# PowerBrick.net
KiCad netlist of a schematic drawn in EAGLE
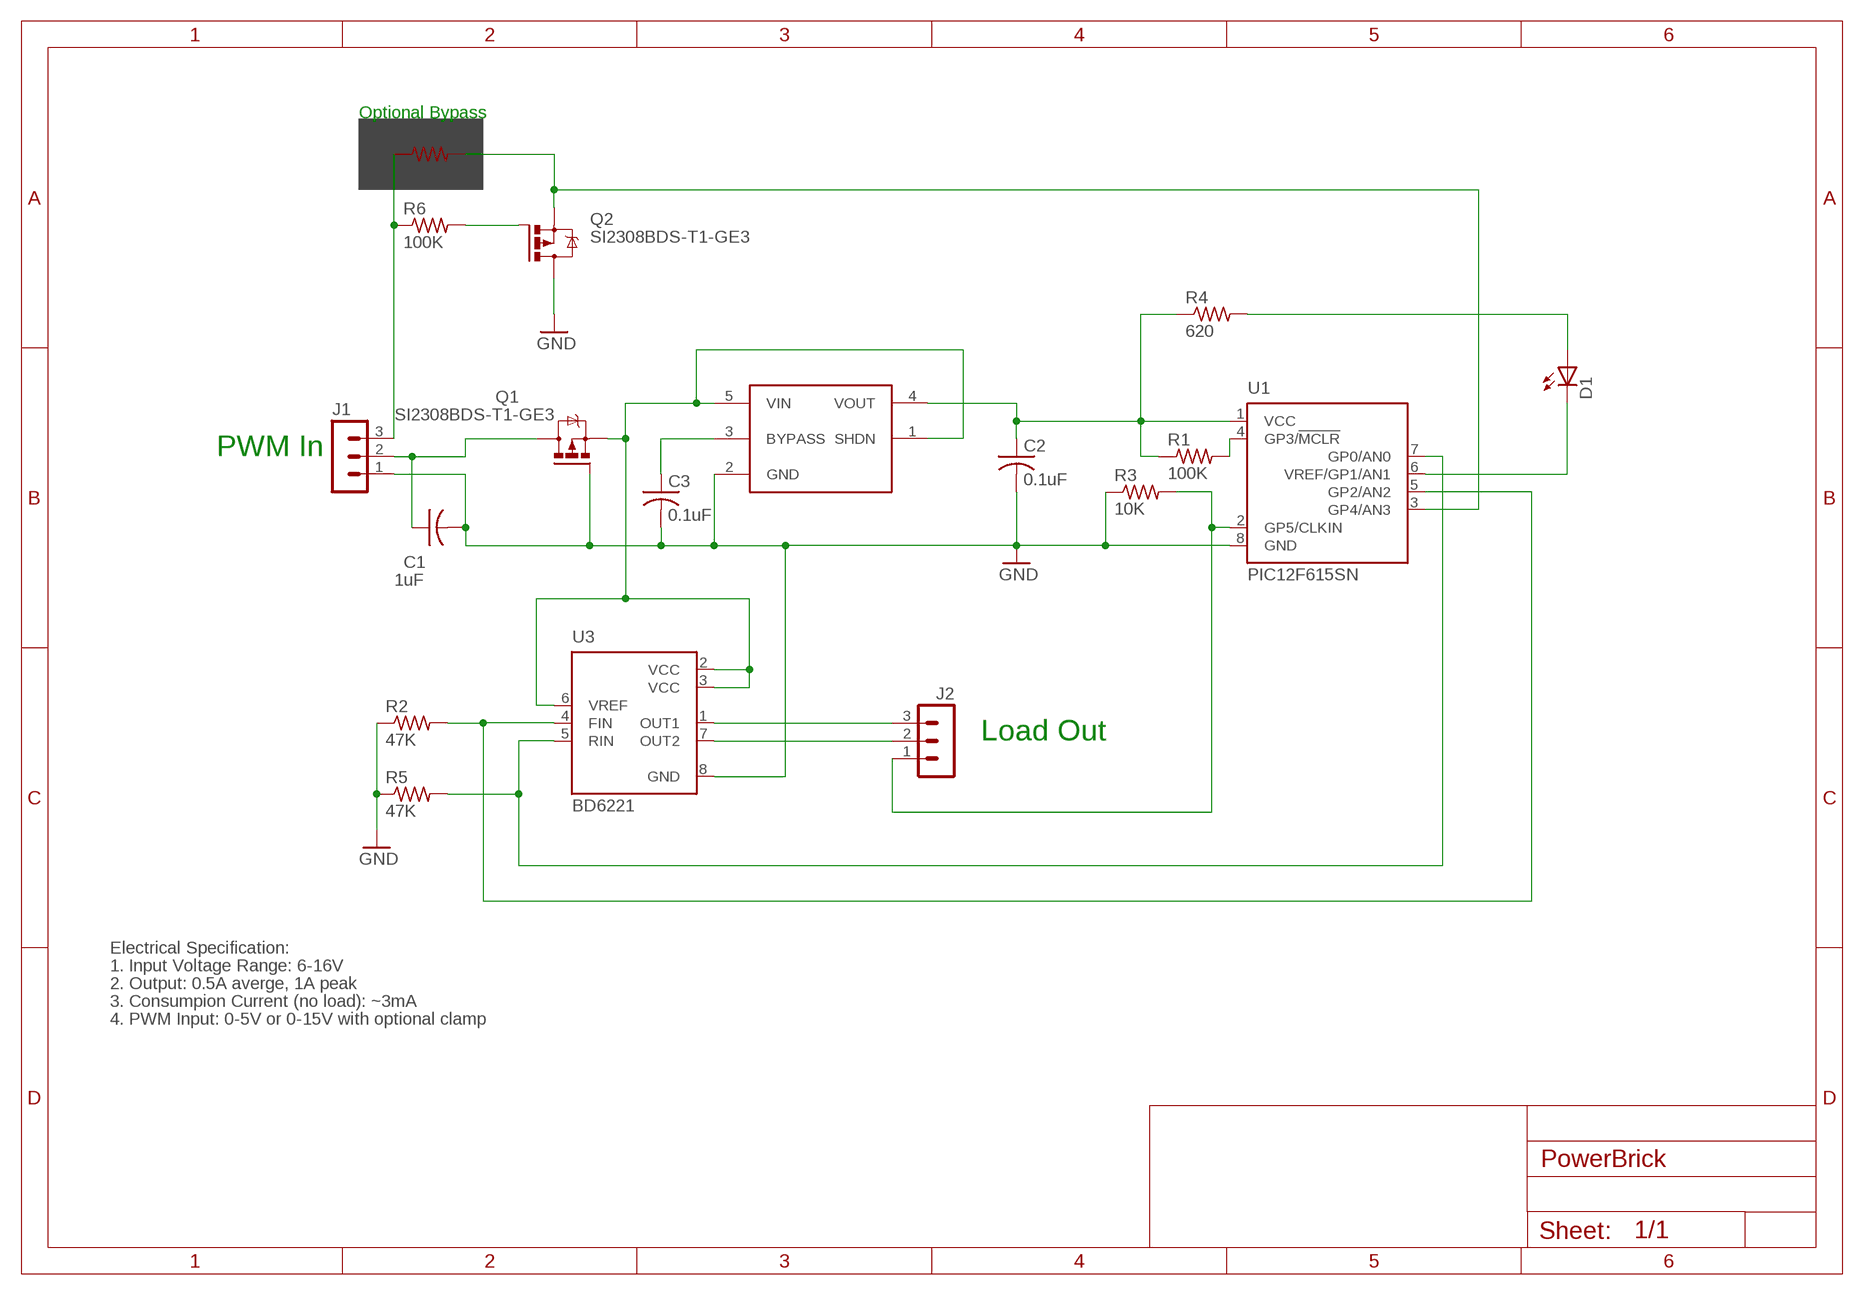
[diagram p0: schematic, sheet 1]

(export (version "E")
  (design (tool "Eeschema 10.0.6"))
  (components
    (comp (ref "C1")
      (value "1uF")
      (footprint "eagle-import:C0805")
      (libsource (lib "eagle-import") (part "C-USC0805"))
    )
    (comp (ref "C2")
      (value "0.1uF")
      (footprint "eagle-import:C0805")
      (libsource (lib "eagle-import") (part "C-USC0805"))
    )
    (comp (ref "C3")
      (value "0.1uF")
      (footprint "eagle-import:C0805")
      (libsource (lib "eagle-import") (part "C-USC0805"))
    )
    (comp (ref "D1")
      (value "LEDCHIPLED_0603")
      (footprint "eagle-import:CHIPLED_0603")
      (libsource (lib "eagle-import") (part "LEDCHIPLED_0603"))
    )
    (comp (ref "J1")
      (value "MA03-1")
      (footprint "eagle-import:MA03-1")
      (libsource (lib "eagle-import") (part "MA03-1"))
    )
    (comp (ref "J2")
      (value "MA03-1")
      (footprint "eagle-import:MA03-1")
      (libsource (lib "eagle-import") (part "MA03-1"))
    )
    (comp (ref "Q1")
      (value "SI2308BDS-T1-GE3")
      (footprint "eagle-import:MICRO3")
      (libsource (lib "eagle-import") (part "IRLML5203"))
    )
    (comp (ref "Q2")
      (value "SI2308BDS-T1-GE3")
      (footprint "eagle-import:MICRO3")
      (libsource (lib "eagle-import") (part "IRLML5203"))
    )
    (comp (ref "R1")
      (value "100K")
      (footprint "eagle-import:R0603")
      (libsource (lib "eagle-import") (part "R-US_R0603"))
    )
    (comp (ref "R2")
      (value "47K")
      (footprint "eagle-import:R0603")
      (libsource (lib "eagle-import") (part "R-US_R0603"))
    )
    (comp (ref "R3")
      (value "10K")
      (footprint "eagle-import:R0603")
      (libsource (lib "eagle-import") (part "R-US_R0603"))
    )
    (comp (ref "R4")
      (value "620")
      (footprint "eagle-import:R0603")
      (libsource (lib "eagle-import") (part "R-US_R0603"))
    )
    (comp (ref "R5")
      (value "47K")
      (footprint "eagle-import:R0603")
      (libsource (lib "eagle-import") (part "R-US_R0603"))
    )
    (comp (ref "R6")
      (value "100K")
      (footprint "eagle-import:R0603")
      (libsource (lib "eagle-import") (part "R-US_R0603"))
    )
    (comp (ref "R7")
      (value "0")
      (footprint "eagle-import:R0603")
      (libsource (lib "eagle-import") (part "R-US_R0603"))
    )
    (comp (ref "U1")
      (value "PIC12F615SN")
      (footprint "eagle-import:SO-08")
      (fields (field (name "MF") "MICROCHIP") (field (name "MPN") "PIC12F675-E/SN"))
      (libsource (lib "eagle-import") (part "PIC12H615SN"))
    )
    (comp (ref "U2")
      (value "LK112M50TR")
      (footprint "eagle-import:SOT23-5L")
      (libsource (lib "eagle-import") (part "LK112M50TR"))
    )
    (comp (ref "U3")
      (value "BD6221")
      (footprint "eagle-import:SOP8")
      (libsource (lib "eagle-import") (part "BD62XXBD6221"))
    )
  )
  (nets
    (net (code "1") (name "GND") (class "Default")
      (node (ref "C1") (pin "2") (pinfunction "2_2") (pintype "passive"))
      (node (ref "C2") (pin "2") (pinfunction "2_2") (pintype "passive"))
      (node (ref "C3") (pin "2") (pinfunction "2_2") (pintype "passive"))
      (node (ref "J1") (pin "1") (pinfunction "1_1") (pintype "passive"))
      (node (ref "Q1") (pin "1") (pinfunction "G_1") (pintype "passive"))
      (node (ref "Q2") (pin "3") (pinfunction "D_3") (pintype "passive"))
      (node (ref "R2") (pin "1") (pinfunction "1_1") (pintype "passive"))
      (node (ref "R3") (pin "1") (pinfunction "1_1") (pintype "passive"))
      (node (ref "R5") (pin "1") (pinfunction "1_1") (pintype "passive"))
      (node (ref "U1") (pin "8") (pinfunction "GND_8") (pintype "power_in"))
      (node (ref "U2") (pin "2") (pinfunction "GND_2") (pintype "bidirectional"))
      (node (ref "U3") (pin "8") (pinfunction "GND_8") (pintype "power_in"))
    )
    (net (code "2") (name "Net-(D1-PadA)") (class "Default")
      (node (ref "D1") (pin "A") (pinfunction "A_A") (pintype "passive"))
      (node (ref "R4") (pin "2") (pinfunction "2_2") (pintype "passive"))
    )
    (net (code "3") (name "Net-(J1-Pad3)") (class "Default")
      (node (ref "J1") (pin "3") (pinfunction "3_3") (pintype "passive"))
      (node (ref "R6") (pin "1") (pinfunction "1_1") (pintype "passive"))
      (node (ref "R7") (pin "1") (pinfunction "1_1") (pintype "passive"))
    )
    (net (code "4") (name "Net-(Q1-D)") (class "Default")
      (node (ref "C1") (pin "1") (pinfunction "1_1") (pintype "passive"))
      (node (ref "J1") (pin "2") (pinfunction "2_2") (pintype "passive"))
      (node (ref "Q1") (pin "3") (pinfunction "D_3") (pintype "passive"))
    )
    (net (code "5") (name "Net-(Q1-S)") (class "Default")
      (node (ref "Q1") (pin "2") (pinfunction "S_2") (pintype "passive"))
      (node (ref "U2") (pin "1") (pinfunction "SHDN_1") (pintype "bidirectional"))
      (node (ref "U2") (pin "5") (pinfunction "VIN_5") (pintype "bidirectional"))
      (node (ref "U3") (pin "2") (pinfunction "VCC_2") (pintype "power_in"))
      (node (ref "U3") (pin "3") (pinfunction "VCC_3") (pintype "power_in"))
      (node (ref "U3") (pin "6") (pinfunction "VREF_6") (pintype "passive"))
    )
    (net (code "6") (name "Net-(Q2-G)") (class "Default")
      (node (ref "Q2") (pin "1") (pinfunction "G_1") (pintype "passive"))
      (node (ref "R6") (pin "2") (pinfunction "2_2") (pintype "passive"))
    )
    (net (code "7") (name "Net-(Q2-S)") (class "Default")
      (node (ref "Q2") (pin "2") (pinfunction "S_2") (pintype "passive"))
      (node (ref "R7") (pin "2") (pinfunction "2_2") (pintype "passive"))
      (node (ref "U1") (pin "3") (pinfunction "GP4/AN3_3") (pintype "bidirectional"))
    )
    (net (code "8") (name "Net-(U1-GP0{slash}AN0)") (class "Default")
      (node (ref "R5") (pin "2") (pinfunction "2_2") (pintype "passive"))
      (node (ref "U1") (pin "7") (pinfunction "GP0/AN0_7") (pintype "bidirectional"))
      (node (ref "U3") (pin "5") (pinfunction "RIN_5") (pintype "input"))
    )
    (net (code "9") (name "Net-(U1-GP2{slash}AN2)") (class "Default")
      (node (ref "R2") (pin "2") (pinfunction "2_2") (pintype "passive"))
      (node (ref "U1") (pin "5") (pinfunction "GP2/AN2_5") (pintype "bidirectional"))
      (node (ref "U3") (pin "4") (pinfunction "FIN_4") (pintype "input"))
    )
    (net (code "10") (name "Net-(U1-GP3{slash}~{MCLR})") (class "Default")
      (node (ref "R1") (pin "2") (pinfunction "2_2") (pintype "passive"))
      (node (ref "U1") (pin "4") (pinfunction "GP3/~{MCLR}_4") (pintype "input"))
    )
    (net (code "11") (name "Net-(U1-GP5{slash}CLKIN)") (class "Default")
      (node (ref "J2") (pin "1") (pinfunction "1_1") (pintype "passive"))
      (node (ref "R3") (pin "2") (pinfunction "2_2") (pintype "passive"))
      (node (ref "U1") (pin "2") (pinfunction "GP5/CLKIN_2") (pintype "bidirectional"))
    )
    (net (code "12") (name "Net-(U1-VCC)") (class "Default")
      (node (ref "C2") (pin "1") (pinfunction "1_1") (pintype "passive"))
      (node (ref "R1") (pin "1") (pinfunction "1_1") (pintype "passive"))
      (node (ref "R4") (pin "1") (pinfunction "1_1") (pintype "passive"))
      (node (ref "U1") (pin "1") (pinfunction "VCC_1") (pintype "power_in"))
      (node (ref "U2") (pin "4") (pinfunction "VOUT_4") (pintype "bidirectional"))
    )
    (net (code "13") (name "Net-(U1-VREF{slash}GP1{slash}AN1)") (class "Default")
      (node (ref "D1") (pin "C") (pinfunction "C_C") (pintype "passive"))
      (node (ref "U1") (pin "6") (pinfunction "VREF/GP1/AN1_6") (pintype "bidirectional"))
    )
    (net (code "14") (name "Net-(U2-BYPASS)") (class "Default")
      (node (ref "C3") (pin "1") (pinfunction "1_1") (pintype "passive"))
      (node (ref "U2") (pin "3") (pinfunction "BYPASS_3") (pintype "bidirectional"))
    )
    (net (code "15") (name "Net-(U3-OUT1)") (class "Default")
      (node (ref "J2") (pin "3") (pinfunction "3_3") (pintype "passive"))
      (node (ref "U3") (pin "1") (pinfunction "OUT1_1") (pintype "output"))
    )
    (net (code "16") (name "Net-(U3-OUT2)") (class "Default")
      (node (ref "J2") (pin "2") (pinfunction "2_2") (pintype "passive"))
      (node (ref "U3") (pin "7") (pinfunction "OUT2_7") (pintype "output"))
    )
  )
)
